# PCB-VU3.net
KiCad netlist of a schematic drawn in EAGLE
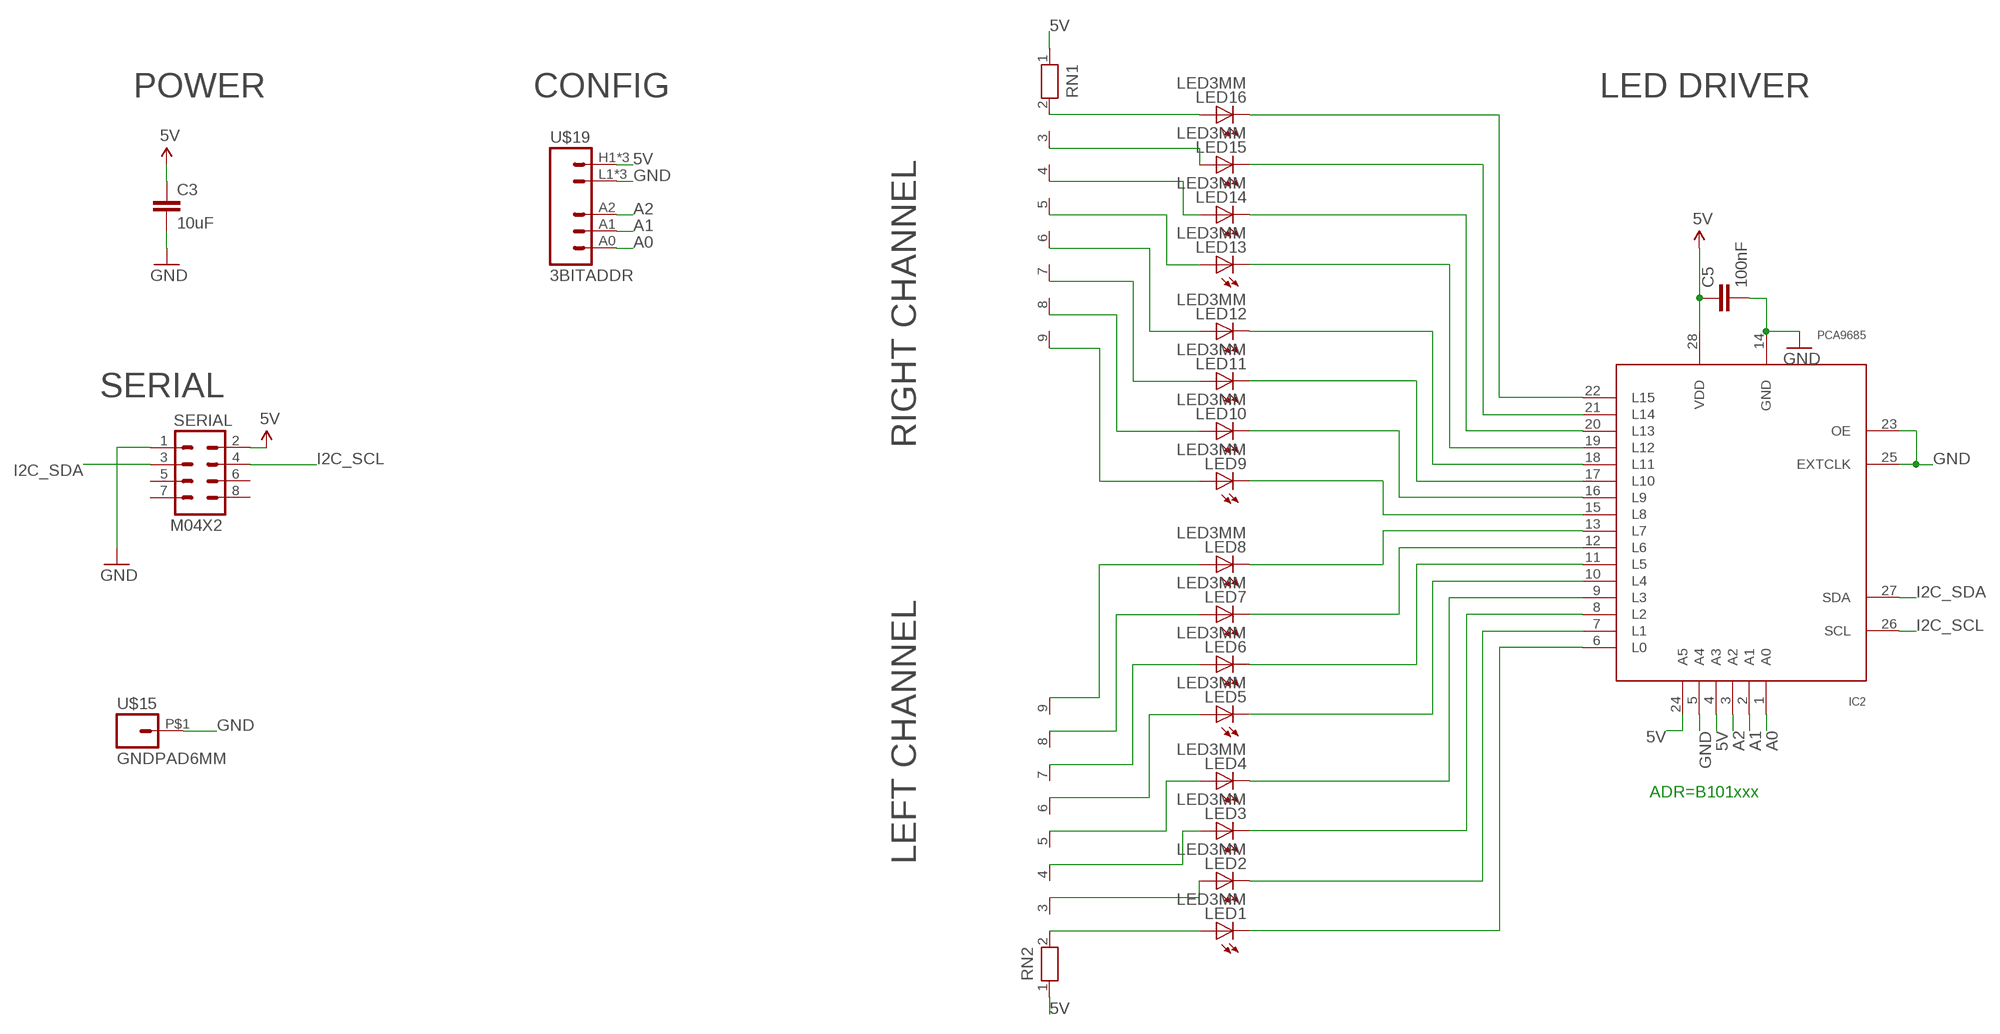
[diagram p0: schematic, sheet 1]

(export (version "E")
  (design (tool "Eeschema 10.0.6"))
  (components
    (comp (ref "C3")
      (value "10uF")
      (footprint "eagle-import:0805")
      (libsource (lib "eagle-import") (part "CAP0805"))
    )
    (comp (ref "C5")
      (value "100nF")
      (footprint "eagle-import:0603-CAP")
      (libsource (lib "eagle-import") (part "CAP0603-CAP"))
    )
    (comp (ref "IC2")
      (value "PCA9685")
      (footprint "eagle-import:TSSOP28")
      (libsource (lib "eagle-import") (part "PCA9685"))
    )
    (comp (ref "LED1")
      (value "LED3MM")
      (footprint "eagle-import:LED3MM")
      (libsource (lib "eagle-import") (part "LED3MM"))
    )
    (comp (ref "LED2")
      (value "LED3MM")
      (footprint "eagle-import:LED3MM")
      (libsource (lib "eagle-import") (part "LED3MM"))
    )
    (comp (ref "LED3")
      (value "LED3MM")
      (footprint "eagle-import:LED3MM")
      (libsource (lib "eagle-import") (part "LED3MM"))
    )
    (comp (ref "LED4")
      (value "LED3MM")
      (footprint "eagle-import:LED3MM")
      (libsource (lib "eagle-import") (part "LED3MM"))
    )
    (comp (ref "LED5")
      (value "LED3MM")
      (footprint "eagle-import:LED3MM")
      (libsource (lib "eagle-import") (part "LED3MM"))
    )
    (comp (ref "LED6")
      (value "LED3MM")
      (footprint "eagle-import:LED3MM")
      (libsource (lib "eagle-import") (part "LED3MM"))
    )
    (comp (ref "LED7")
      (value "LED3MM")
      (footprint "eagle-import:LED3MM")
      (libsource (lib "eagle-import") (part "LED3MM"))
    )
    (comp (ref "LED8")
      (value "LED3MM")
      (footprint "eagle-import:LED3MM")
      (libsource (lib "eagle-import") (part "LED3MM"))
    )
    (comp (ref "LED9")
      (value "LED3MM")
      (footprint "eagle-import:LED3MM")
      (libsource (lib "eagle-import") (part "LED3MM"))
    )
    (comp (ref "LED10")
      (value "LED3MM")
      (footprint "eagle-import:LED3MM")
      (libsource (lib "eagle-import") (part "LED3MM"))
    )
    (comp (ref "LED11")
      (value "LED3MM")
      (footprint "eagle-import:LED3MM")
      (libsource (lib "eagle-import") (part "LED3MM"))
    )
    (comp (ref "LED12")
      (value "LED3MM")
      (footprint "eagle-import:LED3MM")
      (libsource (lib "eagle-import") (part "LED3MM"))
    )
    (comp (ref "LED13")
      (value "LED3MM")
      (footprint "eagle-import:LED3MM")
      (libsource (lib "eagle-import") (part "LED3MM"))
    )
    (comp (ref "LED14")
      (value "LED3MM")
      (footprint "eagle-import:LED3MM")
      (libsource (lib "eagle-import") (part "LED3MM"))
    )
    (comp (ref "LED15")
      (value "LED3MM")
      (footprint "eagle-import:LED3MM")
      (libsource (lib "eagle-import") (part "LED3MM"))
    )
    (comp (ref "LED16")
      (value "LED3MM")
      (footprint "eagle-import:LED3MM")
      (libsource (lib "eagle-import") (part "LED3MM"))
    )
    (comp (ref "RN1")
      (value "RN08")
      (footprint "eagle-import:RN-9")
      (libsource (lib "eagle-import") (part "RN08"))
    )
    (comp (ref "RN2")
      (value "RN08")
      (footprint "eagle-import:RN-9")
      (libsource (lib "eagle-import") (part "RN08"))
    )
    (comp (ref "SERIAL")
      (value "M04X2")
      (footprint "eagle-import:2X4")
      (libsource (lib "eagle-import") (part "M04X2"))
    )
    (comp (ref "U$15")
      (value "GNDPAD6MM")
      (footprint "eagle-import:3.2MMPAD6MM")
      (libsource (lib "eagle-import") (part "GNDPAD6MM"))
    )
    (comp (ref "U$19")
      (value "3BITADDR")
      (footprint "eagle-import:3BITADDR")
      (libsource (lib "eagle-import") (part "3BITADDR"))
    )
  )
  (nets
    (net (code "1") (name "/A0") (class "Default")
      (node (ref "IC2") (pin "1") (pinfunction "A0_1") (pintype "input"))
      (node (ref "U$19") (pin "A0") (pinfunction "A0_A0") (pintype "passive"))
    )
    (net (code "2") (name "/A1") (class "Default")
      (node (ref "IC2") (pin "2") (pinfunction "A1_2") (pintype "input"))
      (node (ref "U$19") (pin "A1") (pinfunction "A1_A1") (pintype "passive"))
    )
    (net (code "3") (name "/A2") (class "Default")
      (node (ref "IC2") (pin "3") (pinfunction "A2_3") (pintype "input"))
      (node (ref "U$19") (pin "A2") (pinfunction "A2_A2") (pintype "passive"))
    )
    (net (code "4") (name "/I2C_SCL") (class "Default")
      (node (ref "IC2") (pin "26") (pinfunction "SCL_26") (pintype "input"))
      (node (ref "SERIAL") (pin "4") (pinfunction "4_4") (pintype "passive"))
    )
    (net (code "5") (name "/I2C_SDA") (class "Default")
      (node (ref "IC2") (pin "27") (pinfunction "SDA_27") (pintype "input"))
      (node (ref "SERIAL") (pin "3") (pinfunction "3_3") (pintype "passive"))
    )
    (net (code "6") (name "5V") (class "Default")
      (node (ref "C3") (pin "1") (pinfunction "1_1") (pintype "passive"))
      (node (ref "C5") (pin "1") (pinfunction "1_1") (pintype "passive"))
      (node (ref "IC2") (pin "24") (pinfunction "A5_24") (pintype "input"))
      (node (ref "IC2") (pin "28") (pinfunction "VDD_28") (pintype "power_in"))
      (node (ref "IC2") (pin "4") (pinfunction "A3_4") (pintype "input"))
      (node (ref "RN1") (pin "1") (pinfunction "1_1") (pintype "passive"))
      (node (ref "RN2") (pin "1") (pinfunction "1_1") (pintype "passive"))
      (node (ref "SERIAL") (pin "2") (pinfunction "2_2") (pintype "passive"))
      (node (ref "U$19") (pin "H1") (pinfunction "VCC_H1") (pintype "passive"))
      (node (ref "U$19") (pin "H2") (pinfunction "VCC_H2") (pintype "passive"))
      (node (ref "U$19") (pin "H3") (pinfunction "VCC_H3") (pintype "passive"))
    )
    (net (code "7") (name "GND") (class "Default")
      (node (ref "C3") (pin "2") (pinfunction "2_2") (pintype "passive"))
      (node (ref "C5") (pin "2") (pinfunction "2_2") (pintype "passive"))
      (node (ref "IC2") (pin "14") (pinfunction "GND_14") (pintype "power_in"))
      (node (ref "IC2") (pin "23") (pinfunction "OE_23") (pintype "input"))
      (node (ref "IC2") (pin "25") (pinfunction "EXTCLK_25") (pintype "input"))
      (node (ref "IC2") (pin "5") (pinfunction "A4_5") (pintype "input"))
      (node (ref "SERIAL") (pin "1") (pinfunction "1_1") (pintype "passive"))
      (node (ref "U$15") (pin "P$1") (pinfunction "1_P$1") (pintype "passive"))
      (node (ref "U$19") (pin "L1") (pinfunction "GND_L1") (pintype "passive"))
      (node (ref "U$19") (pin "L2") (pinfunction "GND_L2") (pintype "passive"))
      (node (ref "U$19") (pin "L3") (pinfunction "GND_L3") (pintype "passive"))
    )
    (net (code "8") (name "Net-(IC2-L0)") (class "Default")
      (node (ref "IC2") (pin "6") (pinfunction "L0_6") (pintype "output"))
      (node (ref "LED1") (pin "K") (pinfunction "C_K") (pintype "passive"))
    )
    (net (code "9") (name "Net-(IC2-L1)") (class "Default")
      (node (ref "IC2") (pin "7") (pinfunction "L1_7") (pintype "output"))
      (node (ref "LED2") (pin "K") (pinfunction "C_K") (pintype "passive"))
    )
    (net (code "10") (name "Net-(IC2-L2)") (class "Default")
      (node (ref "IC2") (pin "8") (pinfunction "L2_8") (pintype "output"))
      (node (ref "LED3") (pin "K") (pinfunction "C_K") (pintype "passive"))
    )
    (net (code "11") (name "Net-(IC2-L3)") (class "Default")
      (node (ref "IC2") (pin "9") (pinfunction "L3_9") (pintype "output"))
      (node (ref "LED4") (pin "K") (pinfunction "C_K") (pintype "passive"))
    )
    (net (code "12") (name "Net-(IC2-L4)") (class "Default")
      (node (ref "IC2") (pin "10") (pinfunction "L4_10") (pintype "output"))
      (node (ref "LED5") (pin "K") (pinfunction "C_K") (pintype "passive"))
    )
    (net (code "13") (name "Net-(IC2-L5)") (class "Default")
      (node (ref "IC2") (pin "11") (pinfunction "L5_11") (pintype "output"))
      (node (ref "LED6") (pin "K") (pinfunction "C_K") (pintype "passive"))
    )
    (net (code "14") (name "Net-(IC2-L6)") (class "Default")
      (node (ref "IC2") (pin "12") (pinfunction "L6_12") (pintype "output"))
      (node (ref "LED7") (pin "K") (pinfunction "C_K") (pintype "passive"))
    )
    (net (code "15") (name "Net-(IC2-L7)") (class "Default")
      (node (ref "IC2") (pin "13") (pinfunction "L7_13") (pintype "output"))
      (node (ref "LED8") (pin "K") (pinfunction "C_K") (pintype "passive"))
    )
    (net (code "16") (name "Net-(IC2-L8)") (class "Default")
      (node (ref "IC2") (pin "15") (pinfunction "L8_15") (pintype "output"))
      (node (ref "LED9") (pin "K") (pinfunction "C_K") (pintype "passive"))
    )
    (net (code "17") (name "Net-(IC2-L9)") (class "Default")
      (node (ref "IC2") (pin "16") (pinfunction "L9_16") (pintype "output"))
      (node (ref "LED10") (pin "K") (pinfunction "C_K") (pintype "passive"))
    )
    (net (code "18") (name "Net-(IC2-L10)") (class "Default")
      (node (ref "IC2") (pin "17") (pinfunction "L10_17") (pintype "output"))
      (node (ref "LED11") (pin "K") (pinfunction "C_K") (pintype "passive"))
    )
    (net (code "19") (name "Net-(IC2-L11)") (class "Default")
      (node (ref "IC2") (pin "18") (pinfunction "L11_18") (pintype "output"))
      (node (ref "LED12") (pin "K") (pinfunction "C_K") (pintype "passive"))
    )
    (net (code "20") (name "Net-(IC2-L12)") (class "Default")
      (node (ref "IC2") (pin "19") (pinfunction "L12_19") (pintype "output"))
      (node (ref "LED13") (pin "K") (pinfunction "C_K") (pintype "passive"))
    )
    (net (code "21") (name "Net-(IC2-L13)") (class "Default")
      (node (ref "IC2") (pin "20") (pinfunction "L13_20") (pintype "output"))
      (node (ref "LED14") (pin "K") (pinfunction "C_K") (pintype "passive"))
    )
    (net (code "22") (name "Net-(IC2-L14)") (class "Default")
      (node (ref "IC2") (pin "21") (pinfunction "L14_21") (pintype "output"))
      (node (ref "LED15") (pin "K") (pinfunction "C_K") (pintype "passive"))
    )
    (net (code "23") (name "Net-(IC2-L15)") (class "Default")
      (node (ref "IC2") (pin "22") (pinfunction "L15_22") (pintype "output"))
      (node (ref "LED16") (pin "K") (pinfunction "C_K") (pintype "passive"))
    )
    (net (code "24") (name "Net-(LED1-PadA)") (class "Default")
      (node (ref "LED1") (pin "A") (pinfunction "A_A") (pintype "passive"))
      (node (ref "RN2") (pin "2") (pinfunction "2_2") (pintype "passive"))
    )
    (net (code "25") (name "Net-(LED2-PadA)") (class "Default")
      (node (ref "LED2") (pin "A") (pinfunction "A_A") (pintype "passive"))
      (node (ref "RN2") (pin "3") (pinfunction "3_3") (pintype "passive"))
    )
    (net (code "26") (name "Net-(LED3-PadA)") (class "Default")
      (node (ref "LED3") (pin "A") (pinfunction "A_A") (pintype "passive"))
      (node (ref "RN2") (pin "4") (pinfunction "4_4") (pintype "passive"))
    )
    (net (code "27") (name "Net-(LED4-PadA)") (class "Default")
      (node (ref "LED4") (pin "A") (pinfunction "A_A") (pintype "passive"))
      (node (ref "RN2") (pin "5") (pinfunction "5_5") (pintype "passive"))
    )
    (net (code "28") (name "Net-(LED5-PadA)") (class "Default")
      (node (ref "LED5") (pin "A") (pinfunction "A_A") (pintype "passive"))
      (node (ref "RN2") (pin "6") (pinfunction "6_6") (pintype "passive"))
    )
    (net (code "29") (name "Net-(LED6-PadA)") (class "Default")
      (node (ref "LED6") (pin "A") (pinfunction "A_A") (pintype "passive"))
      (node (ref "RN2") (pin "7") (pinfunction "7_7") (pintype "passive"))
    )
    (net (code "30") (name "Net-(LED7-PadA)") (class "Default")
      (node (ref "LED7") (pin "A") (pinfunction "A_A") (pintype "passive"))
      (node (ref "RN2") (pin "8") (pinfunction "8_8") (pintype "passive"))
    )
    (net (code "31") (name "Net-(LED8-PadA)") (class "Default")
      (node (ref "LED8") (pin "A") (pinfunction "A_A") (pintype "passive"))
      (node (ref "RN2") (pin "9") (pinfunction "9_9") (pintype "passive"))
    )
    (net (code "32") (name "Net-(LED9-PadA)") (class "Default")
      (node (ref "LED9") (pin "A") (pinfunction "A_A") (pintype "passive"))
      (node (ref "RN1") (pin "9") (pinfunction "9_9") (pintype "passive"))
    )
    (net (code "33") (name "Net-(LED10-PadA)") (class "Default")
      (node (ref "LED10") (pin "A") (pinfunction "A_A") (pintype "passive"))
      (node (ref "RN1") (pin "8") (pinfunction "8_8") (pintype "passive"))
    )
    (net (code "34") (name "Net-(LED11-PadA)") (class "Default")
      (node (ref "LED11") (pin "A") (pinfunction "A_A") (pintype "passive"))
      (node (ref "RN1") (pin "7") (pinfunction "7_7") (pintype "passive"))
    )
    (net (code "35") (name "Net-(LED12-PadA)") (class "Default")
      (node (ref "LED12") (pin "A") (pinfunction "A_A") (pintype "passive"))
      (node (ref "RN1") (pin "6") (pinfunction "6_6") (pintype "passive"))
    )
    (net (code "36") (name "Net-(LED13-PadA)") (class "Default")
      (node (ref "LED13") (pin "A") (pinfunction "A_A") (pintype "passive"))
      (node (ref "RN1") (pin "5") (pinfunction "5_5") (pintype "passive"))
    )
    (net (code "37") (name "Net-(LED14-PadA)") (class "Default")
      (node (ref "LED14") (pin "A") (pinfunction "A_A") (pintype "passive"))
      (node (ref "RN1") (pin "4") (pinfunction "4_4") (pintype "passive"))
    )
    (net (code "38") (name "Net-(LED15-PadA)") (class "Default")
      (node (ref "LED15") (pin "A") (pinfunction "A_A") (pintype "passive"))
      (node (ref "RN1") (pin "3") (pinfunction "3_3") (pintype "passive"))
    )
    (net (code "39") (name "Net-(LED16-PadA)") (class "Default")
      (node (ref "LED16") (pin "A") (pinfunction "A_A") (pintype "passive"))
      (node (ref "RN1") (pin "2") (pinfunction "2_2") (pintype "passive"))
    )
    (net (code "40") (name "unconnected-(SERIAL-Pad5)") (class "Default")
      (node (ref "SERIAL") (pin "5") (pinfunction "5_5") (pintype "passive"))
    )
    (net (code "41") (name "unconnected-(SERIAL-Pad6)") (class "Default")
      (node (ref "SERIAL") (pin "6") (pinfunction "6_6") (pintype "passive"))
    )
    (net (code "42") (name "unconnected-(SERIAL-Pad7)") (class "Default")
      (node (ref "SERIAL") (pin "7") (pinfunction "7_7") (pintype "passive"))
    )
    (net (code "43") (name "unconnected-(SERIAL-Pad8)") (class "Default")
      (node (ref "SERIAL") (pin "8") (pinfunction "8_8") (pintype "passive"))
    )
  )
)
